# Adafruit_QT_Py_ESP32-S3.net
KiCad netlist of a schematic drawn in EAGLE
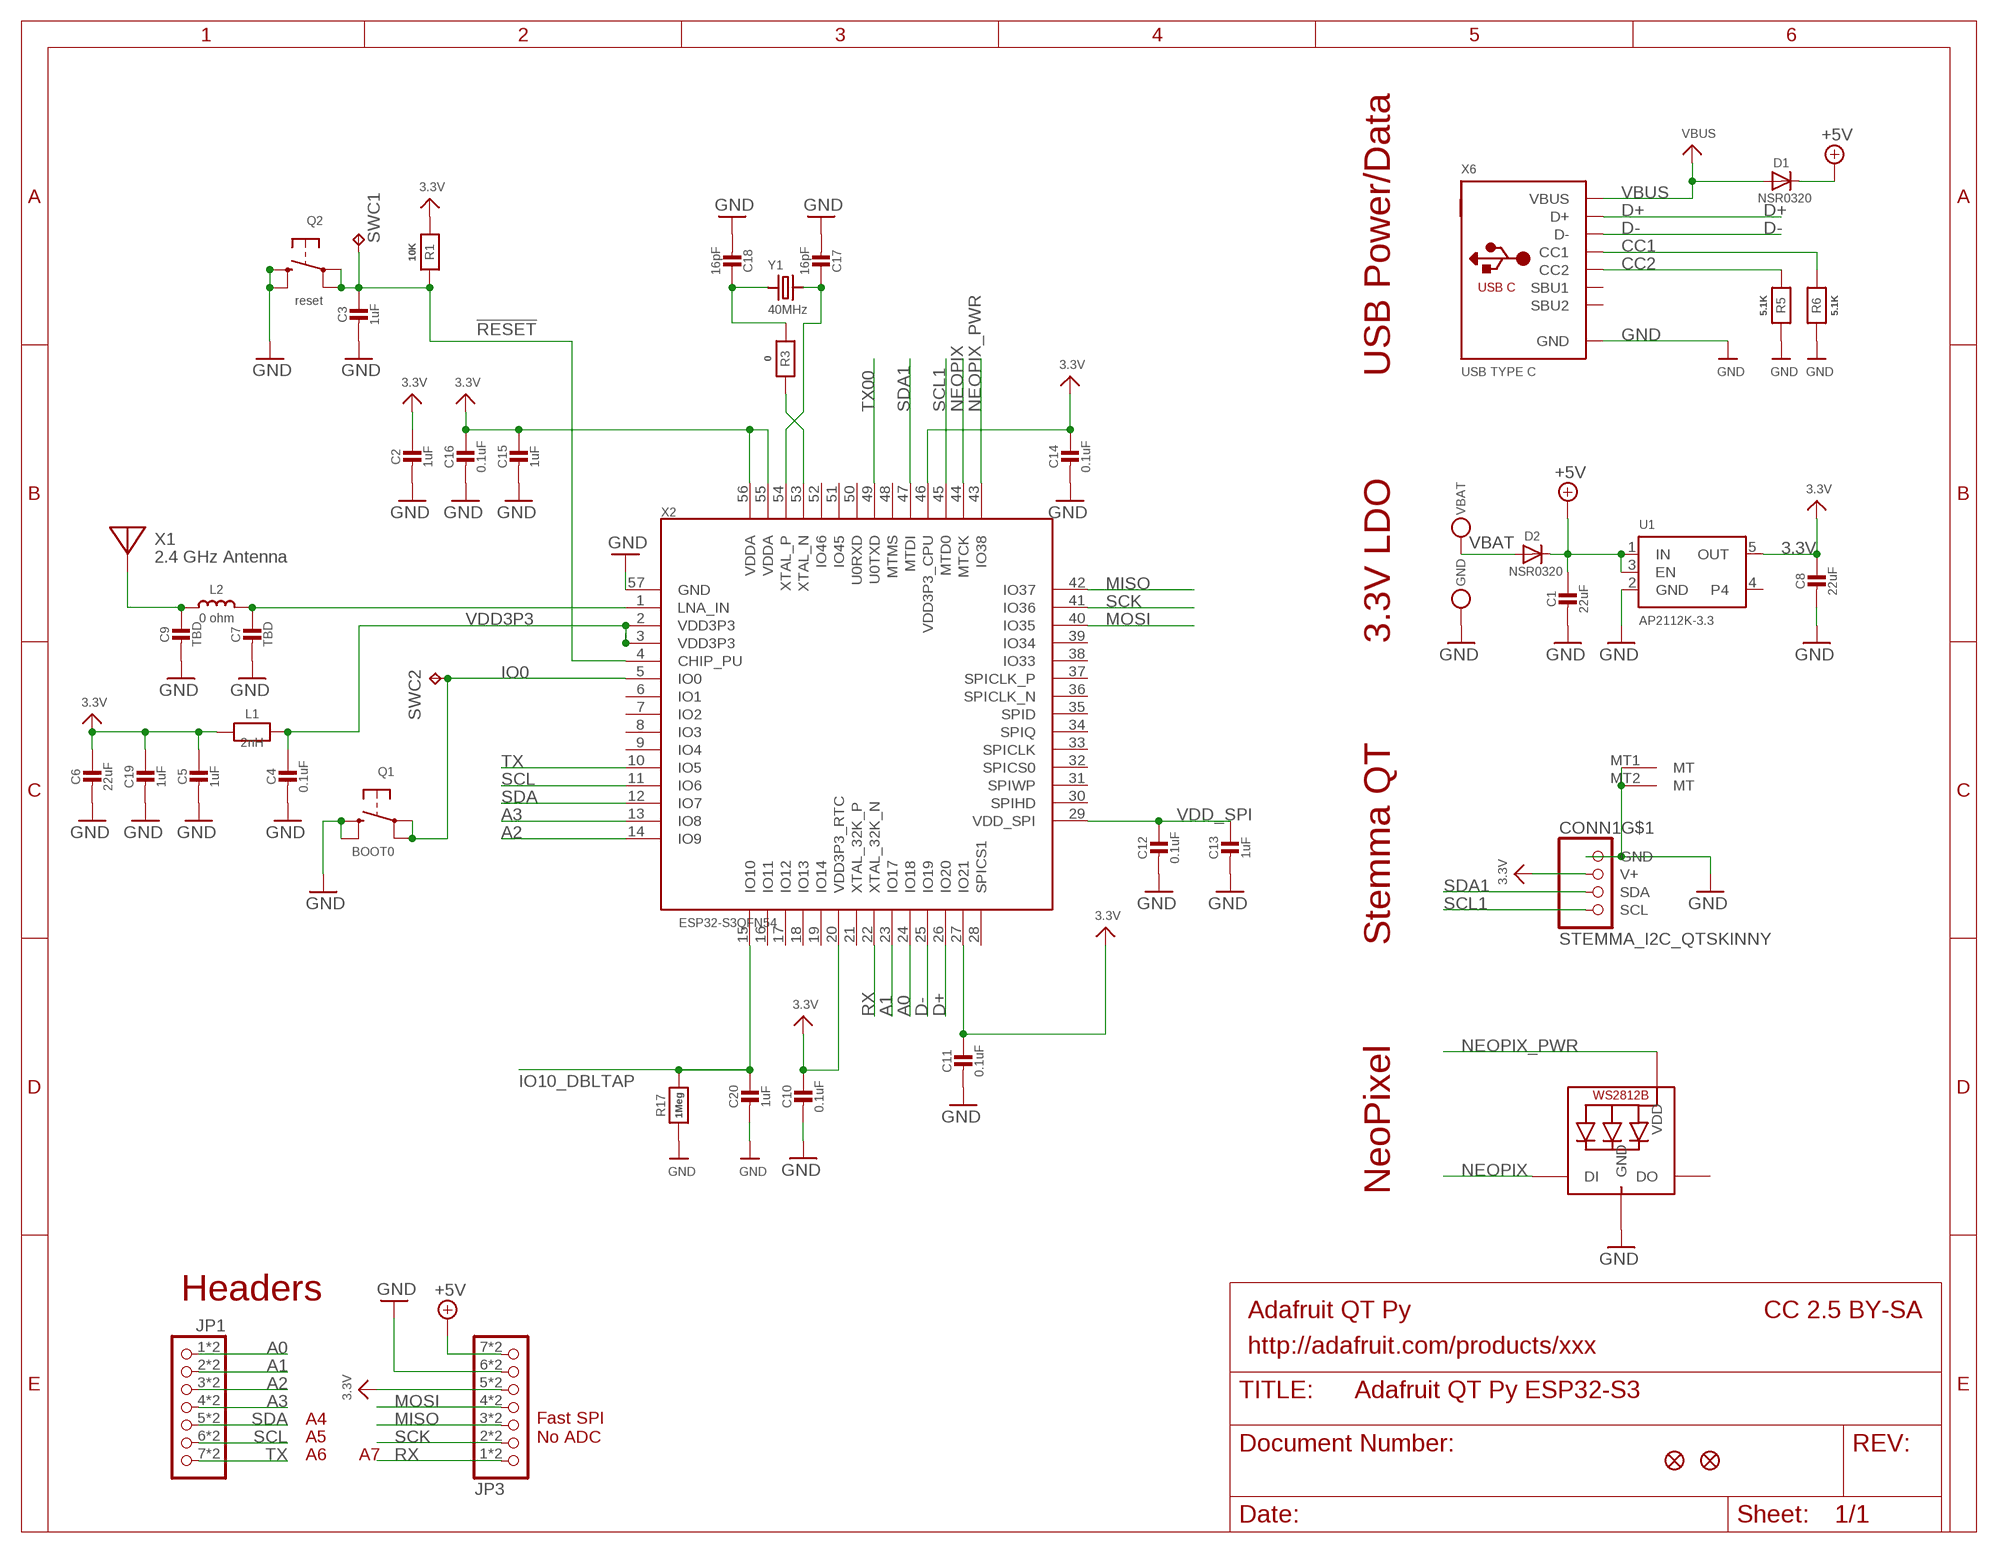
[diagram p0: schematic, sheet 1]

(export (version "E")
  (design (tool "Eeschema 10.0.6"))
  (components
    (comp (ref "C1")
      (value "22uF")
      (footprint "eagle-import:0805-NO")
      (libsource (lib "eagle-import") (part "CAP_CERAMIC0805-NOOUTLINE"))
    )
    (comp (ref "C2")
      (value "1uF")
      (footprint "eagle-import:_0402NO")
      (libsource (lib "eagle-import") (part "CAP_CERAMIC_0402NO"))
    )
    (comp (ref "C3")
      (value "1uF")
      (footprint "eagle-import:_0402NO")
      (libsource (lib "eagle-import") (part "CAP_CERAMIC_0402NO"))
    )
    (comp (ref "C4")
      (value "0.1uF")
      (footprint "eagle-import:_0402NO")
      (libsource (lib "eagle-import") (part "CAP_CERAMIC_0402NO"))
    )
    (comp (ref "C5")
      (value "1uF")
      (footprint "eagle-import:_0402NO")
      (libsource (lib "eagle-import") (part "CAP_CERAMIC_0402NO"))
    )
    (comp (ref "C6")
      (value "22uF")
      (footprint "eagle-import:0805-NO")
      (libsource (lib "eagle-import") (part "CAP_CERAMIC0805-NOOUTLINE"))
    )
    (comp (ref "C7")
      (value "TBD")
      (footprint "eagle-import:_0402NO")
      (libsource (lib "eagle-import") (part "CAP_CERAMIC_0402NO"))
    )
    (comp (ref "C8")
      (value "22uF")
      (footprint "eagle-import:0805-NO")
      (libsource (lib "eagle-import") (part "CAP_CERAMIC0805-NOOUTLINE"))
    )
    (comp (ref "C9")
      (value "TBD")
      (footprint "eagle-import:_0402NO")
      (libsource (lib "eagle-import") (part "CAP_CERAMIC_0402NO"))
    )
    (comp (ref "C10")
      (value "0.1uF")
      (footprint "eagle-import:_0402NO")
      (libsource (lib "eagle-import") (part "CAP_CERAMIC_0402NO"))
    )
    (comp (ref "C11")
      (value "0.1uF")
      (footprint "eagle-import:_0402NO")
      (libsource (lib "eagle-import") (part "CAP_CERAMIC_0402NO"))
    )
    (comp (ref "C12")
      (value "0.1uF")
      (footprint "eagle-import:_0402NO")
      (libsource (lib "eagle-import") (part "CAP_CERAMIC_0402NO"))
    )
    (comp (ref "C13")
      (value "1uF")
      (footprint "eagle-import:_0402NO")
      (libsource (lib "eagle-import") (part "CAP_CERAMIC_0402NO"))
    )
    (comp (ref "C14")
      (value "0.1uF")
      (footprint "eagle-import:_0402NO")
      (libsource (lib "eagle-import") (part "CAP_CERAMIC_0402NO"))
    )
    (comp (ref "C15")
      (value "1uF")
      (footprint "eagle-import:_0402NO")
      (libsource (lib "eagle-import") (part "CAP_CERAMIC_0402NO"))
    )
    (comp (ref "C16")
      (value "0.1uF")
      (footprint "eagle-import:_0402NO")
      (libsource (lib "eagle-import") (part "CAP_CERAMIC_0402NO"))
    )
    (comp (ref "C17")
      (value "16pF")
      (footprint "eagle-import:_0402NO")
      (libsource (lib "eagle-import") (part "CAP_CERAMIC_0402NO"))
    )
    (comp (ref "C18")
      (value "16pF")
      (footprint "eagle-import:_0402NO")
      (libsource (lib "eagle-import") (part "CAP_CERAMIC_0402NO"))
    )
    (comp (ref "C19")
      (value "1uF")
      (footprint "eagle-import:_0402NO")
      (libsource (lib "eagle-import") (part "CAP_CERAMIC_0402NO"))
    )
    (comp (ref "C20")
      (value "1uF")
      (footprint "eagle-import:_0402NO")
      (libsource (lib "eagle-import") (part "CAP_CERAMIC_0402NO"))
    )
    (comp (ref "CONN1")
      (value "STEMMA_I2C_QTSKINNY")
      (footprint "eagle-import:JST_SH4_SKINNY")
      (libsource (lib "eagle-import") (part "STEMMA_I2C_QTSKINNY"))
    )
    (comp (ref "D1")
      (value "NSR0320")
      (footprint "eagle-import:SOD-323_MINI")
      (libsource (lib "eagle-import") (part "DIODE_SOD323MINI"))
    )
    (comp (ref "D2")
      (value "NSR0320")
      (footprint "eagle-import:SOD-323_MINI")
      (libsource (lib "eagle-import") (part "DIODE_SOD323MINI"))
    )
    (comp (ref "GND")
      (value "TESTPOINT_MINUS")
      (footprint "eagle-import:TESTPOINT_MINUS_1X3MM")
      (libsource (lib "eagle-import") (part "TESTPOINT_MINUS"))
    )
    (comp (ref "JP1")
      (value "HEADER-1X7_CASTEL")
      (footprint "eagle-import:1X07_CASTEL")
      (libsource (lib "eagle-import") (part "HEADER-1X7_CASTEL"))
    )
    (comp (ref "JP3")
      (value "HEADER-1X7_CASTEL")
      (footprint "eagle-import:1X07_CASTEL")
      (libsource (lib "eagle-import") (part "HEADER-1X7_CASTEL"))
    )
    (comp (ref "L1")
      (value "2nH")
      (footprint "eagle-import:_0402NO")
      (libsource (lib "eagle-import") (part "RESISTOR_0402NO"))
    )
    (comp (ref "L2")
      (value "0 ohm")
      (footprint "eagle-import:_0402")
      (libsource (lib "eagle-import") (part "INDUCTOR_0402"))
    )
    (comp (ref "LED1")
      (value "WS2812B_SK6805_1515")
      (footprint "eagle-import:SK6805_1515")
      (libsource (lib "eagle-import") (part "WS2812B_SK6805_1515"))
    )
    (comp (ref "Q1")
      (value "BOOT0")
      (footprint "eagle-import:BTN_KMR2_4.6X2.8")
      (libsource (lib "eagle-import") (part "SWITCH_TACT_SMT4.6X2.8"))
    )
    (comp (ref "Q2")
      (value "reset")
      (footprint "eagle-import:BTN_KMR2_4.6X2.8")
      (libsource (lib "eagle-import") (part "SWITCH_TACT_SMT4.6X2.8"))
    )
    (comp (ref "R1")
      (value "10K")
      (footprint "eagle-import:_0402NO")
      (libsource (lib "eagle-import") (part "RESISTOR_0402NO"))
    )
    (comp (ref "R3")
      (value "0")
      (footprint "eagle-import:_0402NO")
      (libsource (lib "eagle-import") (part "RESISTOR_0402NO"))
    )
    (comp (ref "R5")
      (value "5.1K")
      (footprint "eagle-import:_0402NO")
      (libsource (lib "eagle-import") (part "RESISTOR_0402NO"))
    )
    (comp (ref "R6")
      (value "5.1K")
      (footprint "eagle-import:_0402NO")
      (libsource (lib "eagle-import") (part "RESISTOR_0402NO"))
    )
    (comp (ref "R17")
      (value "1Meg")
      (footprint "eagle-import:_0402NO")
      (libsource (lib "eagle-import") (part "RESISTOR_0402NO"))
    )
    (comp (ref "SWC1")
      (value "TPB1,27")
      (footprint "eagle-import:B1,27")
      (libsource (lib "eagle-import") (part "TPB1,27"))
    )
    (comp (ref "SWC2")
      (value "TPB1,27")
      (footprint "eagle-import:B1,27")
      (libsource (lib "eagle-import") (part "TPB1,27"))
    )
    (comp (ref "U$6")
      (value "FIDUCIAL_1MM")
      (footprint "eagle-import:FIDUCIAL_1MM")
      (libsource (lib "eagle-import") (part "FIDUCIAL_1MM"))
    )
    (comp (ref "U$8")
      (value "FIDUCIAL_1MM")
      (footprint "eagle-import:FIDUCIAL_1MM")
      (libsource (lib "eagle-import") (part "FIDUCIAL_1MM"))
    )
    (comp (ref "U1")
      (value "AP2112K-3.3")
      (footprint "eagle-import:SOT23-5")
      (libsource (lib "eagle-import") (part "VREG_SOT23-5"))
    )
    (comp (ref "VBAT")
      (value "TESTPOINT_PLUS13")
      (footprint "eagle-import:TESTPOINT_PLUS_1X3MM")
      (libsource (lib "eagle-import") (part "TESTPOINT_PLUS13"))
    )
    (comp (ref "X1")
      (value "2.4 GHz Antenna")
      (footprint "eagle-import:ANT_2450AT18B100")
      (libsource (lib "eagle-import") (part "ANTENNA_JOHANSON_2450AT18B100"))
    )
    (comp (ref "X2")
      (value "ESP32-S3QFN54")
      (footprint "eagle-import:QFN56_7X7")
      (fields
        (field (name "DIGI-KEY_PART_NUMBER") "1965-ESP32-S2CT-ND")
        (field (name "MF") "Espressif Systems")
        (field (name "MP") "ESP32-S2")
      )
      (libsource (lib "eagle-import") (part "ESP32-S3QFN54"))
    )
    (comp (ref "X6")
      (value "USB TYPE C")
      (footprint "eagle-import:USB_C_CUSB31-CFM2AX-01-X")
      (libsource (lib "eagle-import") (part "USB_C"))
    )
    (comp (ref "Y1")
      (value "40MHz")
      (footprint "eagle-import:CRYSTAL_2X1.6")
      (libsource (lib "eagle-import") (part "CRYSTAL_2X1.6MM"))
    )
  )
  (nets
    (net (code "1") (name "+5V") (class "Default")
      (node (ref "C1") (pin "1") (pinfunction "1_1") (pintype "passive"))
      (node (ref "D1") (pin "C") (pinfunction "C_C") (pintype "passive"))
      (node (ref "D2") (pin "C") (pinfunction "C_C") (pintype "passive"))
      (node (ref "JP3") (pin "7") (pinfunction "7_7") (pintype "passive"))
      (node (ref "JP3") (pin "7C") (pinfunction "7_7C") (pintype "passive"))
      (node (ref "U1") (pin "1") (pinfunction "IN_1") (pintype "power_in"))
      (node (ref "U1") (pin "3") (pinfunction "EN_3") (pintype "input"))
    )
    (net (code "2") (name "/A0") (class "Default")
      (node (ref "JP1") (pin "1") (pinfunction "1_1") (pintype "passive"))
      (node (ref "JP1") (pin "1C") (pinfunction "1_1C") (pintype "passive"))
      (node (ref "X2") (pin "24") (pinfunction "IO18_24") (pintype "bidirectional"))
    )
    (net (code "3") (name "/A1") (class "Default")
      (node (ref "JP1") (pin "2") (pinfunction "2_2") (pintype "passive"))
      (node (ref "JP1") (pin "2C") (pinfunction "2_2C") (pintype "passive"))
      (node (ref "X2") (pin "23") (pinfunction "IO17_23") (pintype "bidirectional"))
    )
    (net (code "4") (name "/A2") (class "Default")
      (node (ref "JP1") (pin "3") (pinfunction "3_3") (pintype "passive"))
      (node (ref "JP1") (pin "3C") (pinfunction "3_3C") (pintype "passive"))
      (node (ref "X2") (pin "14") (pinfunction "IO9_14") (pintype "bidirectional"))
    )
    (net (code "5") (name "/A3") (class "Default")
      (node (ref "JP1") (pin "4") (pinfunction "4_4") (pintype "passive"))
      (node (ref "JP1") (pin "4C") (pinfunction "4_4C") (pintype "passive"))
      (node (ref "X2") (pin "13") (pinfunction "IO8_13") (pintype "bidirectional"))
    )
    (net (code "6") (name "/CC1") (class "Default")
      (node (ref "R6") (pin "2") (pinfunction "2_2") (pintype "passive"))
      (node (ref "X6") (pin "A5") (pinfunction "CC1_A5") (pintype "bidirectional"))
    )
    (net (code "7") (name "/CC2") (class "Default")
      (node (ref "R5") (pin "2") (pinfunction "2_2") (pintype "passive"))
      (node (ref "X6") (pin "B5") (pinfunction "CC2_B5") (pintype "bidirectional"))
    )
    (net (code "8") (name "/D+") (class "Default")
      (node (ref "X2") (pin "26") (pinfunction "IO20_26") (pintype "bidirectional"))
      (node (ref "X6") (pin "A6") (pinfunction "D+_A6") (pintype "bidirectional"))
      (node (ref "X6") (pin "B6") (pinfunction "D+_B6") (pintype "bidirectional"))
    )
    (net (code "9") (name "/D-") (class "Default")
      (node (ref "X2") (pin "25") (pinfunction "IO19_25") (pintype "bidirectional"))
      (node (ref "X6") (pin "A7") (pinfunction "D-_A7") (pintype "bidirectional"))
      (node (ref "X6") (pin "B7") (pinfunction "D-_B7") (pintype "bidirectional"))
    )
    (net (code "10") (name "/IO0") (class "Default")
      (node (ref "Q1") (pin "A") (pinfunction "P_A") (pintype "passive"))
      (node (ref "Q1") (pin "A'") (pinfunction "P1_A'") (pintype "passive"))
      (node (ref "SWC2") (pin "TP") (pinfunction "TP_TP") (pintype "input"))
      (node (ref "X2") (pin "5") (pinfunction "IO0_5") (pintype "bidirectional"))
    )
    (net (code "11") (name "/IO10_DBLTAP") (class "Default")
      (node (ref "C20") (pin "1") (pinfunction "1_1") (pintype "passive"))
      (node (ref "R17") (pin "2") (pinfunction "2_2") (pintype "passive"))
      (node (ref "X2") (pin "15") (pinfunction "IO10_15") (pintype "bidirectional"))
    )
    (net (code "12") (name "/MISO") (class "Default")
      (node (ref "JP3") (pin "3") (pinfunction "3_3") (pintype "passive"))
      (node (ref "JP3") (pin "3C") (pinfunction "3_3C") (pintype "passive"))
      (node (ref "X2") (pin "42") (pinfunction "IO37_42") (pintype "bidirectional"))
    )
    (net (code "13") (name "/MOSI") (class "Default")
      (node (ref "JP3") (pin "4") (pinfunction "4_4") (pintype "passive"))
      (node (ref "JP3") (pin "4C") (pinfunction "4_4C") (pintype "passive"))
      (node (ref "X2") (pin "40") (pinfunction "IO35_40") (pintype "bidirectional"))
    )
    (net (code "14") (name "/NEOPIX") (class "Default")
      (node (ref "LED1") (pin "1") (pinfunction "DI_1") (pintype "input"))
      (node (ref "X2") (pin "44") (pinfunction "MTCK_44") (pintype "bidirectional"))
    )
    (net (code "15") (name "/NEOPIX_PWR") (class "Default")
      (node (ref "LED1") (pin "2") (pinfunction "VDD_2") (pintype "power_in"))
      (node (ref "X2") (pin "43") (pinfunction "IO38_43") (pintype "bidirectional"))
    )
    (net (code "16") (name "/RX") (class "Default")
      (node (ref "JP3") (pin "1") (pinfunction "1_1") (pintype "passive"))
      (node (ref "JP3") (pin "1C") (pinfunction "1_1C") (pintype "passive"))
      (node (ref "X2") (pin "22") (pinfunction "XTAL_32K_N_22") (pintype "bidirectional"))
    )
    (net (code "17") (name "/SCK") (class "Default")
      (node (ref "JP3") (pin "2") (pinfunction "2_2") (pintype "passive"))
      (node (ref "JP3") (pin "2C") (pinfunction "2_2C") (pintype "passive"))
      (node (ref "X2") (pin "41") (pinfunction "IO36_41") (pintype "bidirectional"))
    )
    (net (code "18") (name "/SCL") (class "Default")
      (node (ref "JP1") (pin "6") (pinfunction "6_6") (pintype "passive"))
      (node (ref "JP1") (pin "6C") (pinfunction "6_6C") (pintype "passive"))
      (node (ref "X2") (pin "11") (pinfunction "IO6_11") (pintype "bidirectional"))
    )
    (net (code "19") (name "/SCL1") (class "Default")
      (node (ref "CONN1") (pin "4") (pinfunction "SCL_4") (pintype "passive"))
      (node (ref "X2") (pin "45") (pinfunction "MTD0_45") (pintype "bidirectional"))
    )
    (net (code "20") (name "/SDA") (class "Default")
      (node (ref "JP1") (pin "5") (pinfunction "5_5") (pintype "passive"))
      (node (ref "JP1") (pin "5C") (pinfunction "5_5C") (pintype "passive"))
      (node (ref "X2") (pin "12") (pinfunction "IO7_12") (pintype "bidirectional"))
    )
    (net (code "21") (name "/SDA1") (class "Default")
      (node (ref "CONN1") (pin "3") (pinfunction "SDA_3") (pintype "passive"))
      (node (ref "X2") (pin "47") (pinfunction "MTDI_47") (pintype "bidirectional"))
    )
    (net (code "22") (name "/TX") (class "Default")
      (node (ref "JP1") (pin "7") (pinfunction "7_7") (pintype "passive"))
      (node (ref "JP1") (pin "7C") (pinfunction "7_7C") (pintype "passive"))
      (node (ref "X2") (pin "10") (pinfunction "IO5_10") (pintype "bidirectional"))
    )
    (net (code "23") (name "/TX00") (class "Default")
      (node (ref "X2") (pin "49") (pinfunction "U0TXD_49") (pintype "bidirectional"))
    )
    (net (code "24") (name "/VBAT") (class "Default")
      (node (ref "D2") (pin "A") (pinfunction "A_A") (pintype "passive"))
      (node (ref "VBAT") (pin "P$1") (pinfunction "P$1_P$1") (pintype "bidirectional"))
    )
    (net (code "25") (name "/VDD3P3") (class "Default")
      (node (ref "C4") (pin "1") (pinfunction "1_1") (pintype "passive"))
      (node (ref "L1") (pin "2") (pinfunction "2_2") (pintype "passive"))
      (node (ref "X2") (pin "2") (pinfunction "VDD3P3_2") (pintype "power_in"))
      (node (ref "X2") (pin "3") (pinfunction "VDD3P3_3") (pintype "power_in"))
    )
    (net (code "26") (name "/VDD_SPI") (class "Default")
      (node (ref "C12") (pin "1") (pinfunction "1_1") (pintype "passive"))
      (node (ref "C13") (pin "1") (pinfunction "1_1") (pintype "passive"))
      (node (ref "X2") (pin "29") (pinfunction "VDD_SPI_29") (pintype "power_in"))
    )
    (net (code "27") (name "/~{RESET}") (class "Default")
      (node (ref "C3") (pin "1") (pinfunction "1_1") (pintype "passive"))
      (node (ref "Q2") (pin "A") (pinfunction "P_A") (pintype "passive"))
      (node (ref "Q2") (pin "A'") (pinfunction "P1_A'") (pintype "passive"))
      (node (ref "R1") (pin "2") (pinfunction "2_2") (pintype "passive"))
      (node (ref "SWC1") (pin "TP") (pinfunction "TP_TP") (pintype "input"))
      (node (ref "X2") (pin "4") (pinfunction "CHIP_PU_4") (pintype "input"))
    )
    (net (code "28") (name "3.3V") (class "Default")
      (node (ref "C10") (pin "1") (pinfunction "1_1") (pintype "passive"))
      (node (ref "C11") (pin "1") (pinfunction "1_1") (pintype "passive"))
      (node (ref "C14") (pin "1") (pinfunction "1_1") (pintype "passive"))
      (node (ref "C15") (pin "1") (pinfunction "1_1") (pintype "passive"))
      (node (ref "C16") (pin "1") (pinfunction "1_1") (pintype "passive"))
      (node (ref "C19") (pin "1") (pinfunction "1_1") (pintype "passive"))
      (node (ref "C2") (pin "1") (pinfunction "1_1") (pintype "passive"))
      (node (ref "C5") (pin "1") (pinfunction "1_1") (pintype "passive"))
      (node (ref "C6") (pin "1") (pinfunction "1_1") (pintype "passive"))
      (node (ref "C8") (pin "1") (pinfunction "1_1") (pintype "passive"))
      (node (ref "CONN1") (pin "2") (pinfunction "V+_2") (pintype "passive"))
      (node (ref "JP3") (pin "5") (pinfunction "5_5") (pintype "passive"))
      (node (ref "JP3") (pin "5C") (pinfunction "5_5C") (pintype "passive"))
      (node (ref "L1") (pin "1") (pinfunction "1_1") (pintype "passive"))
      (node (ref "R1") (pin "1") (pinfunction "1_1") (pintype "passive"))
      (node (ref "U1") (pin "5") (pinfunction "OUT_5") (pintype "power_in"))
      (node (ref "X2") (pin "20") (pinfunction "VDD3P3_RTC_20") (pintype "power_in"))
      (node (ref "X2") (pin "27") (pinfunction "IO21_27") (pintype "bidirectional"))
      (node (ref "X2") (pin "46") (pinfunction "VDD3P3_CPU_46") (pintype "power_in"))
      (node (ref "X2") (pin "55") (pinfunction "VDDA_55") (pintype "power_in"))
      (node (ref "X2") (pin "56") (pinfunction "VDDA_56") (pintype "power_in"))
    )
    (net (code "29") (name "GND") (class "Default")
      (node (ref "C1") (pin "2") (pinfunction "2_2") (pintype "passive"))
      (node (ref "C10") (pin "2") (pinfunction "2_2") (pintype "passive"))
      (node (ref "C11") (pin "2") (pinfunction "2_2") (pintype "passive"))
      (node (ref "C12") (pin "2") (pinfunction "2_2") (pintype "passive"))
      (node (ref "C13") (pin "2") (pinfunction "2_2") (pintype "passive"))
      (node (ref "C14") (pin "2") (pinfunction "2_2") (pintype "passive"))
      (node (ref "C15") (pin "2") (pinfunction "2_2") (pintype "passive"))
      (node (ref "C16") (pin "2") (pinfunction "2_2") (pintype "passive"))
      (node (ref "C17") (pin "2") (pinfunction "2_2") (pintype "passive"))
      (node (ref "C18") (pin "2") (pinfunction "2_2") (pintype "passive"))
      (node (ref "C19") (pin "2") (pinfunction "2_2") (pintype "passive"))
      (node (ref "C2") (pin "2") (pinfunction "2_2") (pintype "passive"))
      (node (ref "C20") (pin "2") (pinfunction "2_2") (pintype "passive"))
      (node (ref "C3") (pin "2") (pinfunction "2_2") (pintype "passive"))
      (node (ref "C4") (pin "2") (pinfunction "2_2") (pintype "passive"))
      (node (ref "C5") (pin "2") (pinfunction "2_2") (pintype "passive"))
      (node (ref "C6") (pin "2") (pinfunction "2_2") (pintype "passive"))
      (node (ref "C7") (pin "2") (pinfunction "2_2") (pintype "passive"))
      (node (ref "C8") (pin "2") (pinfunction "2_2") (pintype "passive"))
      (node (ref "C9") (pin "2") (pinfunction "2_2") (pintype "passive"))
      (node (ref "CONN1") (pin "1") (pinfunction "GND_1") (pintype "passive"))
      (node (ref "CONN1") (pin "MT1") (pinfunction "MT_MT1") (pintype "bidirectional"))
      (node (ref "CONN1") (pin "MT2") (pinfunction "MT_MT2") (pintype "bidirectional"))
      (node (ref "GND") (pin "P$1") (pinfunction "P$1_P$1") (pintype "bidirectional"))
      (node (ref "JP3") (pin "6") (pinfunction "6_6") (pintype "passive"))
      (node (ref "JP3") (pin "6C") (pinfunction "6_6C") (pintype "passive"))
      (node (ref "LED1") (pin "4") (pinfunction "GND_4") (pintype "power_in"))
      (node (ref "Q1") (pin "B") (pinfunction "S_B") (pintype "passive"))
      (node (ref "Q1") (pin "B'") (pinfunction "S1_B'") (pintype "passive"))
      (node (ref "Q2") (pin "B") (pinfunction "S_B") (pintype "passive"))
      (node (ref "Q2") (pin "B'") (pinfunction "S1_B'") (pintype "passive"))
      (node (ref "R17") (pin "1") (pinfunction "1_1") (pintype "passive"))
      (node (ref "R5") (pin "1") (pinfunction "1_1") (pintype "passive"))
      (node (ref "R6") (pin "1") (pinfunction "1_1") (pintype "passive"))
      (node (ref "U1") (pin "2") (pinfunction "GND_2") (pintype "power_in"))
      (node (ref "X2") (pin "57") (pinfunction "GND_57") (pintype "power_in"))
      (node (ref "X6") (pin "A1B12") (pinfunction "GND_A1B12") (pintype "power_in"))
      (node (ref "X6") (pin "B1A12") (pinfunction "GND_B1A12") (pintype "power_in"))
    )
    (net (code "30") (name "Net-(C18-Pad1)") (class "Default")
      (node (ref "C18") (pin "1") (pinfunction "1_1") (pintype "passive"))
      (node (ref "R3") (pin "1") (pinfunction "1_1") (pintype "passive"))
      (node (ref "Y1") (pin "1") (pinfunction "1_1") (pintype "passive"))
    )
    (net (code "31") (name "Net-(X1-P$1)") (class "Default")
      (node (ref "C9") (pin "1") (pinfunction "1_1") (pintype "passive"))
      (node (ref "L2") (pin "1") (pinfunction "1_1") (pintype "passive"))
      (node (ref "X1") (pin "FP") (pinfunction "P$1_FP") (pintype "passive"))
    )
    (net (code "32") (name "Net-(X2-LNA_IN)") (class "Default")
      (node (ref "C7") (pin "1") (pinfunction "1_1") (pintype "passive"))
      (node (ref "L2") (pin "2") (pinfunction "2_2") (pintype "passive"))
      (node (ref "X2") (pin "1") (pinfunction "LNA_IN_1") (pintype "bidirectional"))
    )
    (net (code "33") (name "Net-(X2-XTAL_N)") (class "Default")
      (node (ref "R3") (pin "2") (pinfunction "2_2") (pintype "passive"))
      (node (ref "X2") (pin "53") (pinfunction "XTAL_N_53") (pintype "bidirectional"))
    )
    (net (code "34") (name "Net-(X2-XTAL_P)") (class "Default")
      (node (ref "C17") (pin "1") (pinfunction "1_1") (pintype "passive"))
      (node (ref "X2") (pin "54") (pinfunction "XTAL_P_54") (pintype "bidirectional"))
      (node (ref "Y1") (pin "3") (pinfunction "2_3") (pintype "passive"))
    )
    (net (code "35") (name "VBUS") (class "Default")
      (node (ref "D1") (pin "A") (pinfunction "A_A") (pintype "passive"))
      (node (ref "X6") (pin "A4B9") (pinfunction "VBUS_A4B9") (pintype "power_in"))
      (node (ref "X6") (pin "B4A9") (pinfunction "VBUS_B4A9") (pintype "power_in"))
    )
    (net (code "36") (name "unconnected-(LED1-DO-Pad3)") (class "Default")
      (node (ref "LED1") (pin "3") (pinfunction "DO_3") (pintype "output"))
    )
    (net (code "37") (name "unconnected-(U1-P4-Pad4)") (class "Default")
      (node (ref "U1") (pin "4") (pinfunction "P4_4") (pintype "bidirectional"))
    )
    (net (code "38") (name "unconnected-(X2-IO1-Pad6)") (class "Default")
      (node (ref "X2") (pin "6") (pinfunction "IO1_6") (pintype "bidirectional"))
    )
    (net (code "39") (name "unconnected-(X2-IO2-Pad7)") (class "Default")
      (node (ref "X2") (pin "7") (pinfunction "IO2_7") (pintype "bidirectional"))
    )
    (net (code "40") (name "unconnected-(X2-IO3-Pad8)") (class "Default")
      (node (ref "X2") (pin "8") (pinfunction "IO3_8") (pintype "bidirectional"))
    )
    (net (code "41") (name "unconnected-(X2-IO4-Pad9)") (class "Default")
      (node (ref "X2") (pin "9") (pinfunction "IO4_9") (pintype "bidirectional"))
    )
    (net (code "42") (name "unconnected-(X2-IO11-Pad16)") (class "Default")
      (node (ref "X2") (pin "16") (pinfunction "IO11_16") (pintype "bidirectional"))
    )
    (net (code "43") (name "unconnected-(X2-IO12-Pad17)") (class "Default")
      (node (ref "X2") (pin "17") (pinfunction "IO12_17") (pintype "bidirectional"))
    )
    (net (code "44") (name "unconnected-(X2-IO13-Pad18)") (class "Default")
      (node (ref "X2") (pin "18") (pinfunction "IO13_18") (pintype "bidirectional"))
    )
    (net (code "45") (name "unconnected-(X2-IO14-Pad19)") (class "Default")
      (node (ref "X2") (pin "19") (pinfunction "IO14_19") (pintype "bidirectional"))
    )
    (net (code "46") (name "unconnected-(X2-IO33-Pad38)") (class "Default")
      (node (ref "X2") (pin "38") (pinfunction "IO33_38") (pintype "bidirectional"))
    )
    (net (code "47") (name "unconnected-(X2-IO34-Pad39)") (class "Default")
      (node (ref "X2") (pin "39") (pinfunction "IO34_39") (pintype "bidirectional"))
    )
    (net (code "48") (name "unconnected-(X2-IO45-Pad51)") (class "Default")
      (node (ref "X2") (pin "51") (pinfunction "IO45_51") (pintype "bidirectional"))
    )
    (net (code "49") (name "unconnected-(X2-IO46-Pad52)") (class "Default")
      (node (ref "X2") (pin "52") (pinfunction "IO46_52") (pintype "input"))
    )
    (net (code "50") (name "unconnected-(X2-MTMS-Pad48)") (class "Default")
      (node (ref "X2") (pin "48") (pinfunction "MTMS_48") (pintype "bidirectional"))
    )
    (net (code "51") (name "unconnected-(X2-SPICLK-Pad33)") (class "Default")
      (node (ref "X2") (pin "33") (pinfunction "SPICLK_33") (pintype "bidirectional"))
    )
    (net (code "52") (name "unconnected-(X2-SPICLK_N-Pad36)") (class "Default")
      (node (ref "X2") (pin "36") (pinfunction "SPICLK_N_36") (pintype "bidirectional"))
    )
    (net (code "53") (name "unconnected-(X2-SPICLK_P-Pad37)") (class "Default")
      (node (ref "X2") (pin "37") (pinfunction "SPICLK_P_37") (pintype "bidirectional"))
    )
    (net (code "54") (name "unconnected-(X2-SPICS0-Pad32)") (class "Default")
      (node (ref "X2") (pin "32") (pinfunction "SPICS0_32") (pintype "bidirectional"))
    )
    (net (code "55") (name "unconnected-(X2-SPICS1-Pad28)") (class "Default")
      (node (ref "X2") (pin "28") (pinfunction "SPICS1_28") (pintype "bidirectional"))
    )
    (net (code "56") (name "unconnected-(X2-SPID-Pad35)") (class "Default")
      (node (ref "X2") (pin "35") (pinfunction "SPID_35") (pintype "bidirectional"))
    )
    (net (code "57") (name "unconnected-(X2-SPIHD-Pad30)") (class "Default")
      (node (ref "X2") (pin "30") (pinfunction "SPIHD_30") (pintype "bidirectional"))
    )
    (net (code "58") (name "unconnected-(X2-SPIQ-Pad34)") (class "Default")
      (node (ref "X2") (pin "34") (pinfunction "SPIQ_34") (pintype "bidirectional"))
    )
    (net (code "59") (name "unconnected-(X2-SPIWP-Pad31)") (class "Default")
      (node (ref "X2") (pin "31") (pinfunction "SPIWP_31") (pintype "bidirectional"))
    )
    (net (code "60") (name "unconnected-(X2-U0RXD-Pad50)") (class "Default")
      (node (ref "X2") (pin "50") (pinfunction "U0RXD_50") (pintype "bidirectional"))
    )
    (net (code "61") (name "unconnected-(X2-XTAL_32K_P-Pad21)") (class "Default")
      (node (ref "X2") (pin "21") (pinfunction "XTAL_32K_P_21") (pintype "bidirectional"))
    )
    (net (code "62") (name "unconnected-(X6-SBU1-PadA8)") (class "Default")
      (node (ref "X6") (pin "A8") (pinfunction "SBU1_A8") (pintype "bidirectional"))
    )
    (net (code "63") (name "unconnected-(X6-SBU2-PadB8)") (class "Default")
      (node (ref "X6") (pin "B8") (pinfunction "SBU2_B8") (pintype "bidirectional"))
    )
  )
)
